# mainboard.net
KiCad netlist of a schematic drawn in EAGLE
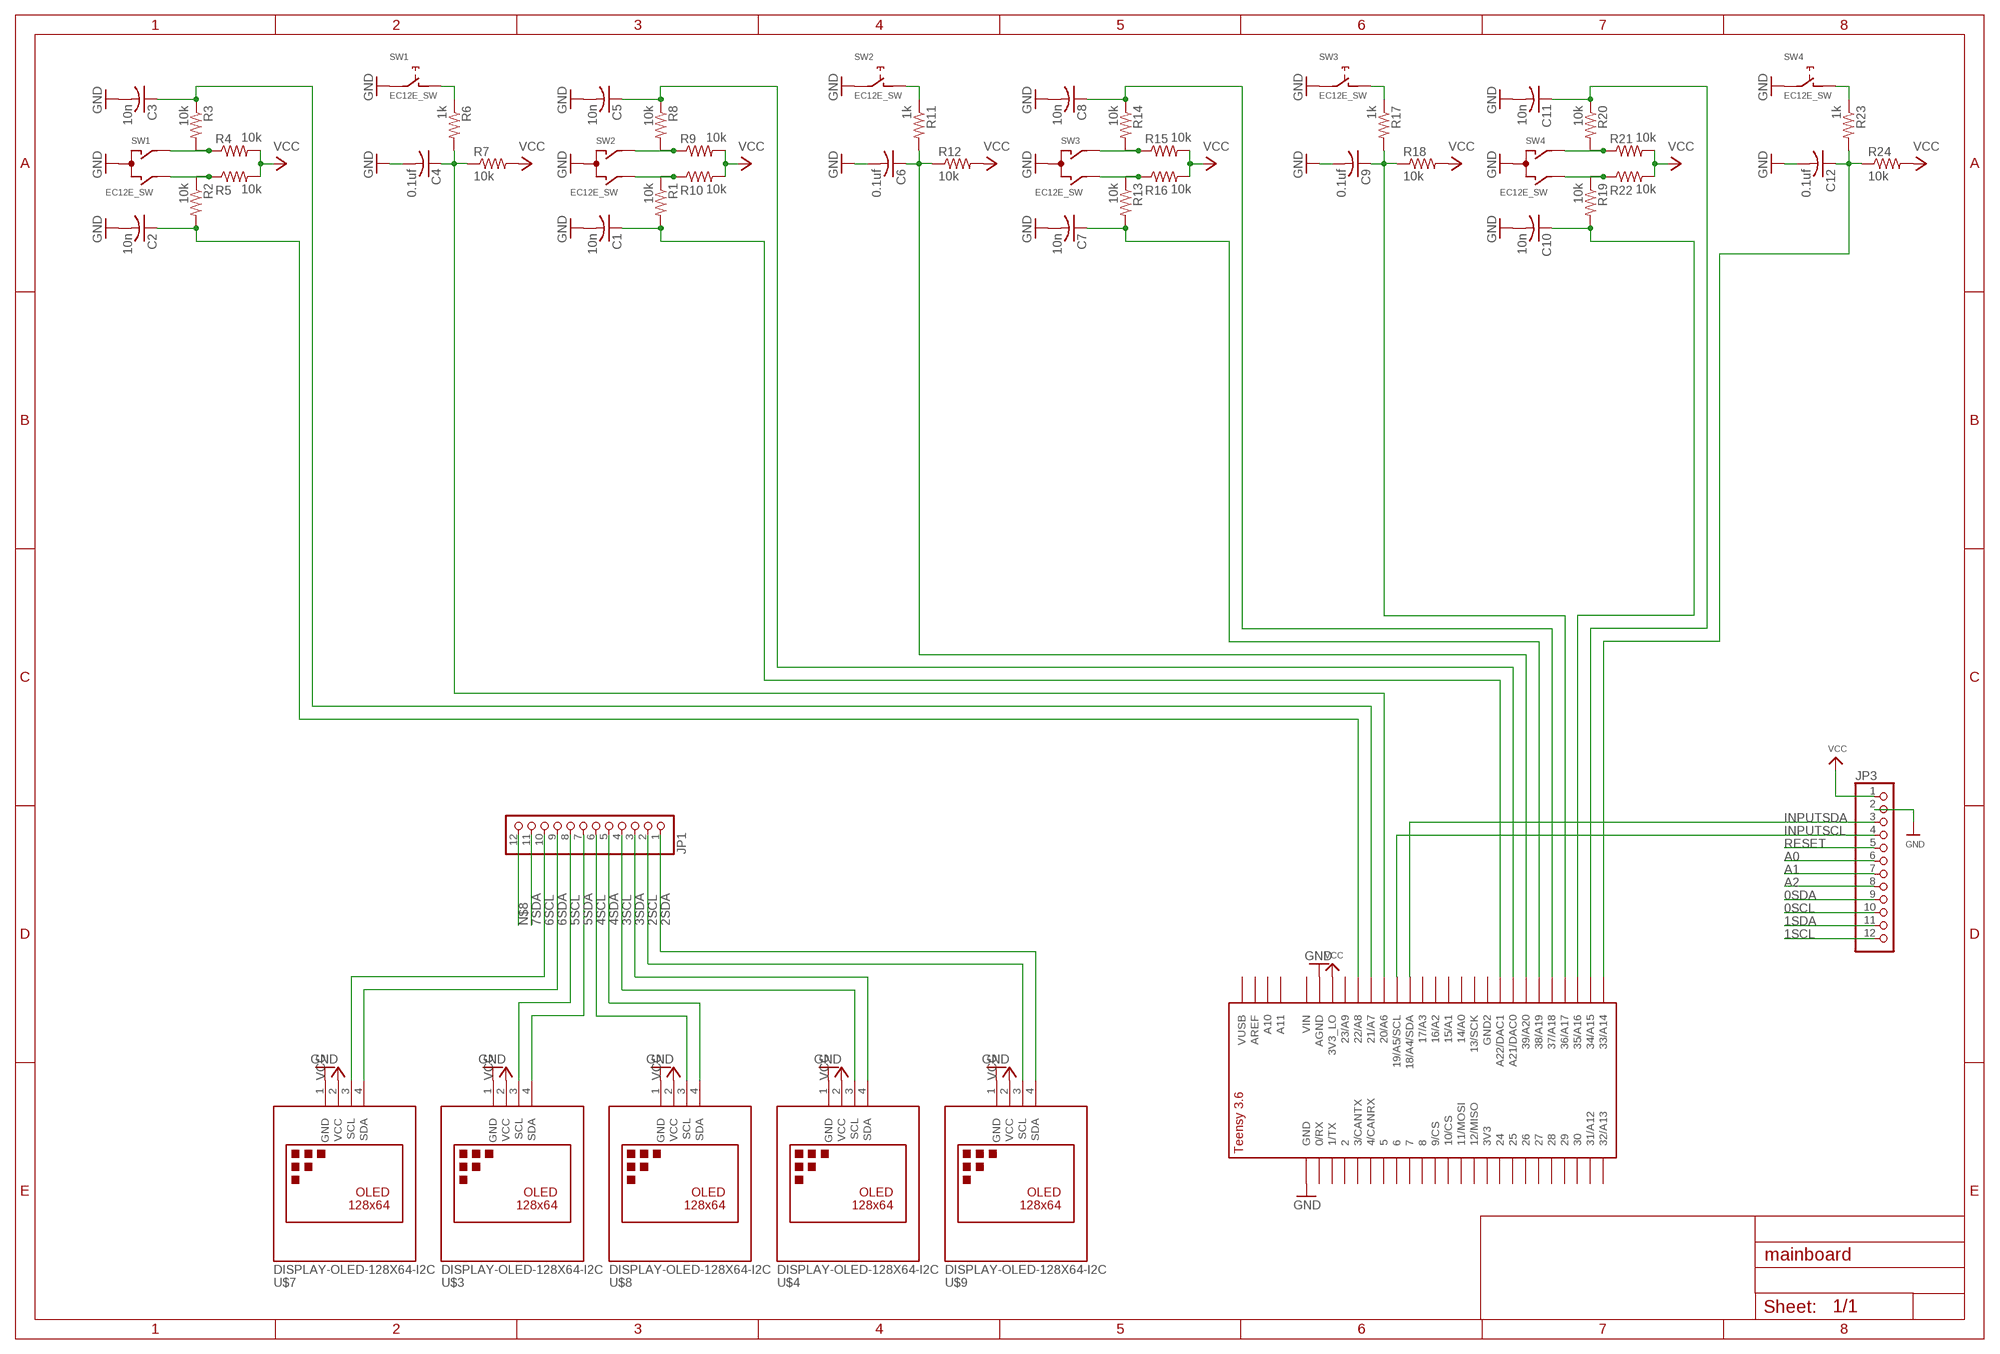
[diagram p0: schematic, sheet 1]

(export (version "E")
  (design (tool "Eeschema 10.0.6"))
  (components
    (comp (ref "C1")
      (value "10n")
      (footprint "eagle-import:C050-025X075")
      (libsource (lib "eagle-import") (part "C-US050-025X075"))
    )
    (comp (ref "C2")
      (value "10n")
      (footprint "eagle-import:C050-025X075")
      (libsource (lib "eagle-import") (part "C-US050-025X075"))
    )
    (comp (ref "C3")
      (value "10n")
      (footprint "eagle-import:C050-025X075")
      (libsource (lib "eagle-import") (part "C-US050-025X075"))
    )
    (comp (ref "C4")
      (value "0.1uf")
      (footprint "eagle-import:C050-025X075")
      (libsource (lib "eagle-import") (part "C-US050-025X075"))
    )
    (comp (ref "C5")
      (value "10n")
      (footprint "eagle-import:C050-025X075")
      (libsource (lib "eagle-import") (part "C-US050-025X075"))
    )
    (comp (ref "C6")
      (value "0.1uf")
      (footprint "eagle-import:C050-025X075")
      (libsource (lib "eagle-import") (part "C-US050-025X075"))
    )
    (comp (ref "C7")
      (value "10n")
      (footprint "eagle-import:C050-025X075")
      (libsource (lib "eagle-import") (part "C-US050-025X075"))
    )
    (comp (ref "C8")
      (value "10n")
      (footprint "eagle-import:C050-025X075")
      (libsource (lib "eagle-import") (part "C-US050-025X075"))
    )
    (comp (ref "C9")
      (value "0.1uf")
      (footprint "eagle-import:C050-025X075")
      (libsource (lib "eagle-import") (part "C-US050-025X075"))
    )
    (comp (ref "C10")
      (value "10n")
      (footprint "eagle-import:C050-025X075")
      (libsource (lib "eagle-import") (part "C-US050-025X075"))
    )
    (comp (ref "C11")
      (value "10n")
      (footprint "eagle-import:C050-025X075")
      (libsource (lib "eagle-import") (part "C-US050-025X075"))
    )
    (comp (ref "C12")
      (value "0.1uf")
      (footprint "eagle-import:C050-025X075")
      (libsource (lib "eagle-import") (part "C-US050-025X075"))
    )
    (comp (ref "JP1")
      (value "HEADER-1X12")
      (footprint "eagle-import:1X12_ROUND")
      (libsource (lib "eagle-import") (part "HEADER-1X12"))
    )
    (comp (ref "JP3")
      (value "HEADER-1X12")
      (footprint "eagle-import:1X12_ROUND")
      (libsource (lib "eagle-import") (part "HEADER-1X12"))
    )
    (comp (ref "R1")
      (value "10k")
      (footprint "eagle-import:0207_9")
      (libsource (lib "eagle-import") (part "R-US_0207/9"))
    )
    (comp (ref "R2")
      (value "10k")
      (footprint "eagle-import:0207_9")
      (libsource (lib "eagle-import") (part "R-US_0207/9"))
    )
    (comp (ref "R3")
      (value "10k")
      (footprint "eagle-import:0207_9")
      (libsource (lib "eagle-import") (part "R-US_0207/9"))
    )
    (comp (ref "R4")
      (value "10k")
      (footprint "eagle-import:0207_9")
      (libsource (lib "eagle-import") (part "R-US_0207/9"))
    )
    (comp (ref "R5")
      (value "10k")
      (footprint "eagle-import:0207_9")
      (libsource (lib "eagle-import") (part "R-US_0207/9"))
    )
    (comp (ref "R6")
      (value "1k")
      (footprint "eagle-import:0207_9")
      (libsource (lib "eagle-import") (part "R-US_0207/9"))
    )
    (comp (ref "R7")
      (value "10k")
      (footprint "eagle-import:0207_9")
      (libsource (lib "eagle-import") (part "R-US_0207/9"))
    )
    (comp (ref "R8")
      (value "10k")
      (footprint "eagle-import:0207_9")
      (libsource (lib "eagle-import") (part "R-US_0207/9"))
    )
    (comp (ref "R9")
      (value "10k")
      (footprint "eagle-import:0207_9")
      (libsource (lib "eagle-import") (part "R-US_0207/9"))
    )
    (comp (ref "R10")
      (value "10k")
      (footprint "eagle-import:0207_9")
      (libsource (lib "eagle-import") (part "R-US_0207/9"))
    )
    (comp (ref "R11")
      (value "1k")
      (footprint "eagle-import:0207_9")
      (libsource (lib "eagle-import") (part "R-US_0207/9"))
    )
    (comp (ref "R12")
      (value "10k")
      (footprint "eagle-import:0207_9")
      (libsource (lib "eagle-import") (part "R-US_0207/9"))
    )
    (comp (ref "R13")
      (value "10k")
      (footprint "eagle-import:0207_9")
      (libsource (lib "eagle-import") (part "R-US_0207/9"))
    )
    (comp (ref "R14")
      (value "10k")
      (footprint "eagle-import:0207_9")
      (libsource (lib "eagle-import") (part "R-US_0207/9"))
    )
    (comp (ref "R15")
      (value "10k")
      (footprint "eagle-import:0207_9")
      (libsource (lib "eagle-import") (part "R-US_0207/9"))
    )
    (comp (ref "R16")
      (value "10k")
      (footprint "eagle-import:0207_9")
      (libsource (lib "eagle-import") (part "R-US_0207/9"))
    )
    (comp (ref "R17")
      (value "1k")
      (footprint "eagle-import:0207_9")
      (libsource (lib "eagle-import") (part "R-US_0207/9"))
    )
    (comp (ref "R18")
      (value "10k")
      (footprint "eagle-import:0207_9")
      (libsource (lib "eagle-import") (part "R-US_0207/9"))
    )
    (comp (ref "R19")
      (value "10k")
      (footprint "eagle-import:0207_9")
      (libsource (lib "eagle-import") (part "R-US_0207/9"))
    )
    (comp (ref "R20")
      (value "10k")
      (footprint "eagle-import:0207_9")
      (libsource (lib "eagle-import") (part "R-US_0207/9"))
    )
    (comp (ref "R21")
      (value "10k")
      (footprint "eagle-import:0207_9")
      (libsource (lib "eagle-import") (part "R-US_0207/9"))
    )
    (comp (ref "R22")
      (value "10k")
      (footprint "eagle-import:0207_9")
      (libsource (lib "eagle-import") (part "R-US_0207/9"))
    )
    (comp (ref "R23")
      (value "1k")
      (footprint "eagle-import:0207_9")
      (libsource (lib "eagle-import") (part "R-US_0207/9"))
    )
    (comp (ref "R24")
      (value "10k")
      (footprint "eagle-import:0207_9")
      (libsource (lib "eagle-import") (part "R-US_0207/9"))
    )
    (comp (ref "SW1")
      (value "EC12E_SW")
      (footprint "eagle-import:ALPS_EC12E_SW")
      (fields (field (name "MPN") "EC12E2424407"))
      (libsource (lib "eagle-import") (part "EC12E_SW"))
    )
    (comp (ref "SW2")
      (value "EC12E_SW")
      (footprint "eagle-import:ALPS_EC12E_SW")
      (fields (field (name "MPN") "EC12E2424407"))
      (libsource (lib "eagle-import") (part "EC12E_SW"))
    )
    (comp (ref "SW3")
      (value "EC12E_SW")
      (footprint "eagle-import:ALPS_EC12E_SW")
      (fields (field (name "MPN") "EC12E2424407"))
      (libsource (lib "eagle-import") (part "EC12E_SW"))
    )
    (comp (ref "SW4")
      (value "EC12E_SW")
      (footprint "eagle-import:ALPS_EC12E_SW")
      (fields (field (name "MPN") "EC12E2424407"))
      (libsource (lib "eagle-import") (part "EC12E_SW"))
    )
    (comp (ref "U$1")
      (value "TEENSY_3.5/3.6_BASIC")
      (footprint "eagle-import:TEENSY_3.5_3.6_BASIC")
      (libsource (lib "eagle-import") (part "TEENSY_3.5/3.6_BASIC"))
    )
    (comp (ref "U$3")
      (value "DISPLAY-OLED-128X64-I2C")
      (footprint "eagle-import:DISPLAY-OLED-128X64-I2C")
      (libsource (lib "eagle-import") (part "DISPLAY-OLED-128X64-I2C"))
    )
    (comp (ref "U$4")
      (value "DISPLAY-OLED-128X64-I2C")
      (footprint "eagle-import:DISPLAY-OLED-128X64-I2C")
      (libsource (lib "eagle-import") (part "DISPLAY-OLED-128X64-I2C"))
    )
    (comp (ref "U$7")
      (value "DISPLAY-OLED-128X64-I2C")
      (footprint "eagle-import:DISPLAY-OLED-128X64-I2C")
      (libsource (lib "eagle-import") (part "DISPLAY-OLED-128X64-I2C"))
    )
    (comp (ref "U$8")
      (value "DISPLAY-OLED-128X64-I2C")
      (footprint "eagle-import:DISPLAY-OLED-128X64-I2C")
      (libsource (lib "eagle-import") (part "DISPLAY-OLED-128X64-I2C"))
    )
    (comp (ref "U$9")
      (value "DISPLAY-OLED-128X64-I2C")
      (footprint "eagle-import:DISPLAY-OLED-128X64-I2C")
      (libsource (lib "eagle-import") (part "DISPLAY-OLED-128X64-I2C"))
    )
  )
  (nets
    (net (code "1") (name "/0SCL") (class "Default")
      (node (ref "JP3") (pin "10") (pinfunction "10_10") (pintype "passive"))
    )
    (net (code "2") (name "/0SDA") (class "Default")
      (node (ref "JP3") (pin "9") (pinfunction "9_9") (pintype "passive"))
    )
    (net (code "3") (name "/1SCL") (class "Default")
      (node (ref "JP3") (pin "12") (pinfunction "12_12") (pintype "passive"))
    )
    (net (code "4") (name "/1SDA") (class "Default")
      (node (ref "JP3") (pin "11") (pinfunction "11_11") (pintype "passive"))
    )
    (net (code "5") (name "/2SCL") (class "Default")
      (node (ref "JP1") (pin "2") (pinfunction "2_2") (pintype "passive"))
      (node (ref "U$9") (pin "3") (pinfunction "SCL_3") (pintype "bidirectional"))
    )
    (net (code "6") (name "/2SDA") (class "Default")
      (node (ref "JP1") (pin "1") (pinfunction "1_1") (pintype "passive"))
      (node (ref "U$9") (pin "4") (pinfunction "SDA_4") (pintype "bidirectional"))
    )
    (net (code "7") (name "/3SCL") (class "Default")
      (node (ref "JP1") (pin "4") (pinfunction "4_4") (pintype "passive"))
      (node (ref "U$4") (pin "3") (pinfunction "SCL_3") (pintype "bidirectional"))
    )
    (net (code "8") (name "/3SDA") (class "Default")
      (node (ref "JP1") (pin "3") (pinfunction "3_3") (pintype "passive"))
      (node (ref "U$4") (pin "4") (pinfunction "SDA_4") (pintype "bidirectional"))
    )
    (net (code "9") (name "/4SCL") (class "Default")
      (node (ref "JP1") (pin "6") (pinfunction "6_6") (pintype "passive"))
      (node (ref "U$8") (pin "3") (pinfunction "SCL_3") (pintype "bidirectional"))
    )
    (net (code "10") (name "/4SDA") (class "Default")
      (node (ref "JP1") (pin "5") (pinfunction "5_5") (pintype "passive"))
      (node (ref "U$8") (pin "4") (pinfunction "SDA_4") (pintype "bidirectional"))
    )
    (net (code "11") (name "/5SCL") (class "Default")
      (node (ref "JP1") (pin "8") (pinfunction "8_8") (pintype "passive"))
      (node (ref "U$3") (pin "3") (pinfunction "SCL_3") (pintype "bidirectional"))
    )
    (net (code "12") (name "/5SDA") (class "Default")
      (node (ref "JP1") (pin "7") (pinfunction "7_7") (pintype "passive"))
      (node (ref "U$3") (pin "4") (pinfunction "SDA_4") (pintype "bidirectional"))
    )
    (net (code "13") (name "/6SCL") (class "Default")
      (node (ref "JP1") (pin "10") (pinfunction "10_10") (pintype "passive"))
      (node (ref "U$7") (pin "3") (pinfunction "SCL_3") (pintype "bidirectional"))
    )
    (net (code "14") (name "/6SDA") (class "Default")
      (node (ref "JP1") (pin "9") (pinfunction "9_9") (pintype "passive"))
      (node (ref "U$7") (pin "4") (pinfunction "SDA_4") (pintype "bidirectional"))
    )
    (net (code "15") (name "/7SDA") (class "Default")
      (node (ref "JP1") (pin "11") (pinfunction "11_11") (pintype "passive"))
    )
    (net (code "16") (name "/A0") (class "Default")
      (node (ref "JP3") (pin "6") (pinfunction "6_6") (pintype "passive"))
    )
    (net (code "17") (name "/A1") (class "Default")
      (node (ref "JP3") (pin "7") (pinfunction "7_7") (pintype "passive"))
    )
    (net (code "18") (name "/A2") (class "Default")
      (node (ref "JP3") (pin "8") (pinfunction "8_8") (pintype "passive"))
    )
    (net (code "19") (name "/INPUTSCL") (class "Default")
      (node (ref "JP3") (pin "4") (pinfunction "4_4") (pintype "passive"))
      (node (ref "U$1") (pin "19/A5/SCL") (pinfunction "19/A5/SCL_19/A5/SCL") (pintype "bidirectional"))
    )
    (net (code "20") (name "/INPUTSDA") (class "Default")
      (node (ref "JP3") (pin "3") (pinfunction "3_3") (pintype "passive"))
      (node (ref "U$1") (pin "18/A4/SDA") (pinfunction "18/A4/SDA_18/A4/SDA") (pintype "bidirectional"))
    )
    (net (code "21") (name "/N$8") (class "Default")
      (node (ref "JP1") (pin "12") (pinfunction "12_12") (pintype "passive"))
    )
    (net (code "22") (name "/RESET") (class "Default")
      (node (ref "JP3") (pin "5") (pinfunction "5_5") (pintype "passive"))
    )
    (net (code "23") (name "GND") (class "Default")
      (node (ref "C1") (pin "2") (pinfunction "2_2") (pintype "passive"))
      (node (ref "C10") (pin "2") (pinfunction "2_2") (pintype "passive"))
      (node (ref "C11") (pin "2") (pinfunction "2_2") (pintype "passive"))
      (node (ref "C12") (pin "2") (pinfunction "2_2") (pintype "passive"))
      (node (ref "C2") (pin "2") (pinfunction "2_2") (pintype "passive"))
      (node (ref "C3") (pin "2") (pinfunction "2_2") (pintype "passive"))
      (node (ref "C4") (pin "2") (pinfunction "2_2") (pintype "passive"))
      (node (ref "C5") (pin "2") (pinfunction "2_2") (pintype "passive"))
      (node (ref "C6") (pin "2") (pinfunction "2_2") (pintype "passive"))
      (node (ref "C7") (pin "2") (pinfunction "2_2") (pintype "passive"))
      (node (ref "C8") (pin "2") (pinfunction "2_2") (pintype "passive"))
      (node (ref "C9") (pin "2") (pinfunction "2_2") (pintype "passive"))
      (node (ref "JP3") (pin "2") (pinfunction "2_2") (pintype "passive"))
      (node (ref "SW1") (pin "C") (pinfunction "C_C") (pintype "passive"))
      (node (ref "SW1") (pin "E") (pinfunction "2_E") (pintype "passive"))
      (node (ref "SW2") (pin "C") (pinfunction "C_C") (pintype "passive"))
      (node (ref "SW2") (pin "E") (pinfunction "2_E") (pintype "passive"))
      (node (ref "SW3") (pin "C") (pinfunction "C_C") (pintype "passive"))
      (node (ref "SW3") (pin "E") (pinfunction "2_E") (pintype "passive"))
      (node (ref "SW4") (pin "C") (pinfunction "C_C") (pintype "passive"))
      (node (ref "SW4") (pin "E") (pinfunction "2_E") (pintype "passive"))
      (node (ref "U$1") (pin "AGND") (pinfunction "AGND_AGND") (pintype "bidirectional"))
      (node (ref "U$1") (pin "GND") (pinfunction "GND_GND") (pintype "bidirectional"))
      (node (ref "U$3") (pin "1") (pinfunction "GND_1") (pintype "power_in"))
      (node (ref "U$4") (pin "1") (pinfunction "GND_1") (pintype "power_in"))
      (node (ref "U$7") (pin "1") (pinfunction "GND_1") (pintype "power_in"))
      (node (ref "U$8") (pin "1") (pinfunction "GND_1") (pintype "power_in"))
      (node (ref "U$9") (pin "1") (pinfunction "GND_1") (pintype "power_in"))
    )
    (net (code "24") (name "Net-(C1-Pad1)") (class "Default")
      (node (ref "C1") (pin "1") (pinfunction "1_1") (pintype "passive"))
      (node (ref "R1") (pin "2") (pinfunction "2_2") (pintype "passive"))
      (node (ref "U$1") (pin "A22/DAC1") (pinfunction "A22/DAC1_A22/DAC1") (pintype "bidirectional"))
    )
    (net (code "25") (name "Net-(C2-Pad1)") (class "Default")
      (node (ref "C2") (pin "1") (pinfunction "1_1") (pintype "passive"))
      (node (ref "R2") (pin "2") (pinfunction "2_2") (pintype "passive"))
      (node (ref "U$1") (pin "22/A8") (pinfunction "22/A8_22/A8") (pintype "bidirectional"))
    )
    (net (code "26") (name "Net-(C3-Pad1)") (class "Default")
      (node (ref "C3") (pin "1") (pinfunction "1_1") (pintype "passive"))
      (node (ref "R3") (pin "1") (pinfunction "1_1") (pintype "passive"))
      (node (ref "U$1") (pin "21/A7") (pinfunction "21/A7_21/A7") (pintype "bidirectional"))
    )
    (net (code "27") (name "Net-(C4-Pad1)") (class "Default")
      (node (ref "C4") (pin "1") (pinfunction "1_1") (pintype "passive"))
      (node (ref "R6") (pin "2") (pinfunction "2_2") (pintype "passive"))
      (node (ref "R7") (pin "1") (pinfunction "1_1") (pintype "passive"))
      (node (ref "U$1") (pin "20/A6") (pinfunction "20/A6_20/A6") (pintype "bidirectional"))
    )
    (net (code "28") (name "Net-(C6-Pad1)") (class "Default")
      (node (ref "C6") (pin "1") (pinfunction "1_1") (pintype "passive"))
      (node (ref "R11") (pin "2") (pinfunction "2_2") (pintype "passive"))
      (node (ref "R12") (pin "1") (pinfunction "1_1") (pintype "passive"))
      (node (ref "U$1") (pin "39/A20") (pinfunction "39/A20_39/A20") (pintype "bidirectional"))
    )
    (net (code "29") (name "Net-(C7-Pad1)") (class "Default")
      (node (ref "C7") (pin "1") (pinfunction "1_1") (pintype "passive"))
      (node (ref "R13") (pin "2") (pinfunction "2_2") (pintype "passive"))
      (node (ref "U$1") (pin "38/A19") (pinfunction "38/A19_38/A19") (pintype "bidirectional"))
    )
    (net (code "30") (name "Net-(C8-Pad1)") (class "Default")
      (node (ref "C8") (pin "1") (pinfunction "1_1") (pintype "passive"))
      (node (ref "R14") (pin "1") (pinfunction "1_1") (pintype "passive"))
      (node (ref "U$1") (pin "37/A18") (pinfunction "37/A18_37/A18") (pintype "bidirectional"))
    )
    (net (code "31") (name "Net-(C9-Pad1)") (class "Default")
      (node (ref "C9") (pin "1") (pinfunction "1_1") (pintype "passive"))
      (node (ref "R17") (pin "2") (pinfunction "2_2") (pintype "passive"))
      (node (ref "R18") (pin "1") (pinfunction "1_1") (pintype "passive"))
      (node (ref "U$1") (pin "36/A17") (pinfunction "36/A17_36/A17") (pintype "bidirectional"))
    )
    (net (code "32") (name "Net-(C10-Pad1)") (class "Default")
      (node (ref "C10") (pin "1") (pinfunction "1_1") (pintype "passive"))
      (node (ref "R19") (pin "2") (pinfunction "2_2") (pintype "passive"))
      (node (ref "U$1") (pin "35/A16") (pinfunction "35/A16_35/A16") (pintype "bidirectional"))
    )
    (net (code "33") (name "Net-(C11-Pad1)") (class "Default")
      (node (ref "C11") (pin "1") (pinfunction "1_1") (pintype "passive"))
      (node (ref "R20") (pin "1") (pinfunction "1_1") (pintype "passive"))
      (node (ref "U$1") (pin "34/A15") (pinfunction "34/A15_34/A15") (pintype "bidirectional"))
    )
    (net (code "34") (name "Net-(C12-Pad1)") (class "Default")
      (node (ref "C12") (pin "1") (pinfunction "1_1") (pintype "passive"))
      (node (ref "R23") (pin "2") (pinfunction "2_2") (pintype "passive"))
      (node (ref "R24") (pin "1") (pinfunction "1_1") (pintype "passive"))
      (node (ref "U$1") (pin "33/A14") (pinfunction "33/A14_33/A14") (pintype "bidirectional"))
    )
    (net (code "35") (name "Net-(R1-Pad1)") (class "Default")
      (node (ref "R1") (pin "1") (pinfunction "1_1") (pintype "passive"))
      (node (ref "R10") (pin "1") (pinfunction "1_1") (pintype "passive"))
      (node (ref "SW2") (pin "B") (pinfunction "B_B") (pintype "passive"))
    )
    (net (code "36") (name "Net-(R2-Pad1)") (class "Default")
      (node (ref "R2") (pin "1") (pinfunction "1_1") (pintype "passive"))
      (node (ref "R5") (pin "1") (pinfunction "1_1") (pintype "passive"))
      (node (ref "SW1") (pin "B") (pinfunction "B_B") (pintype "passive"))
    )
    (net (code "37") (name "Net-(R3-Pad2)") (class "Default")
      (node (ref "R3") (pin "2") (pinfunction "2_2") (pintype "passive"))
      (node (ref "R4") (pin "1") (pinfunction "1_1") (pintype "passive"))
      (node (ref "SW1") (pin "A") (pinfunction "A_A") (pintype "passive"))
    )
    (net (code "38") (name "Net-(R8-Pad2)") (class "Default")
      (node (ref "R8") (pin "2") (pinfunction "2_2") (pintype "passive"))
      (node (ref "R9") (pin "1") (pinfunction "1_1") (pintype "passive"))
      (node (ref "SW2") (pin "A") (pinfunction "A_A") (pintype "passive"))
    )
    (net (code "39") (name "Net-(R13-Pad1)") (class "Default")
      (node (ref "R13") (pin "1") (pinfunction "1_1") (pintype "passive"))
      (node (ref "R16") (pin "1") (pinfunction "1_1") (pintype "passive"))
      (node (ref "SW3") (pin "B") (pinfunction "B_B") (pintype "passive"))
    )
    (net (code "40") (name "Net-(R14-Pad2)") (class "Default")
      (node (ref "R14") (pin "2") (pinfunction "2_2") (pintype "passive"))
      (node (ref "R15") (pin "1") (pinfunction "1_1") (pintype "passive"))
      (node (ref "SW3") (pin "A") (pinfunction "A_A") (pintype "passive"))
    )
    (net (code "41") (name "Net-(R19-Pad1)") (class "Default")
      (node (ref "R19") (pin "1") (pinfunction "1_1") (pintype "passive"))
      (node (ref "R22") (pin "1") (pinfunction "1_1") (pintype "passive"))
      (node (ref "SW4") (pin "B") (pinfunction "B_B") (pintype "passive"))
    )
    (net (code "42") (name "Net-(R20-Pad2)") (class "Default")
      (node (ref "R20") (pin "2") (pinfunction "2_2") (pintype "passive"))
      (node (ref "R21") (pin "1") (pinfunction "1_1") (pintype "passive"))
      (node (ref "SW4") (pin "A") (pinfunction "A_A") (pintype "passive"))
    )
    (net (code "43") (name "Net-(SW1B-1)") (class "Default")
      (node (ref "R6") (pin "1") (pinfunction "1_1") (pintype "passive"))
      (node (ref "SW1") (pin "D") (pinfunction "1_D") (pintype "passive"))
    )
    (net (code "44") (name "Net-(SW2B-1)") (class "Default")
      (node (ref "R11") (pin "1") (pinfunction "1_1") (pintype "passive"))
      (node (ref "SW2") (pin "D") (pinfunction "1_D") (pintype "passive"))
    )
    (net (code "45") (name "Net-(SW3B-1)") (class "Default")
      (node (ref "R17") (pin "1") (pinfunction "1_1") (pintype "passive"))
      (node (ref "SW3") (pin "D") (pinfunction "1_D") (pintype "passive"))
    )
    (net (code "46") (name "Net-(SW4B-1)") (class "Default")
      (node (ref "R23") (pin "1") (pinfunction "1_1") (pintype "passive"))
      (node (ref "SW4") (pin "D") (pinfunction "1_D") (pintype "passive"))
    )
    (net (code "47") (name "Net-(U$1-A21{slash}DAC0)") (class "Default")
      (node (ref "C5") (pin "1") (pinfunction "1_1") (pintype "passive"))
      (node (ref "R8") (pin "1") (pinfunction "1_1") (pintype "passive"))
      (node (ref "U$1") (pin "21/DAC0") (pinfunction "A21/DAC0_21/DAC0") (pintype "bidirectional"))
    )
    (net (code "48") (name "VCC") (class "Default")
      (node (ref "JP3") (pin "1") (pinfunction "1_1") (pintype "passive"))
      (node (ref "R10") (pin "2") (pinfunction "2_2") (pintype "passive"))
      (node (ref "R12") (pin "2") (pinfunction "2_2") (pintype "passive"))
      (node (ref "R15") (pin "2") (pinfunction "2_2") (pintype "passive"))
      (node (ref "R16") (pin "2") (pinfunction "2_2") (pintype "passive"))
      (node (ref "R18") (pin "2") (pinfunction "2_2") (pintype "passive"))
      (node (ref "R21") (pin "2") (pinfunction "2_2") (pintype "passive"))
      (node (ref "R22") (pin "2") (pinfunction "2_2") (pintype "passive"))
      (node (ref "R24") (pin "2") (pinfunction "2_2") (pintype "passive"))
      (node (ref "R4") (pin "2") (pinfunction "2_2") (pintype "passive"))
      (node (ref "R5") (pin "2") (pinfunction "2_2") (pintype "passive"))
      (node (ref "R7") (pin "2") (pinfunction "2_2") (pintype "passive"))
      (node (ref "R9") (pin "2") (pinfunction "2_2") (pintype "passive"))
      (node (ref "U$1") (pin "3V3_LO") (pinfunction "3V3_LO_3V3_LO") (pintype "bidirectional"))
      (node (ref "U$3") (pin "2") (pinfunction "VCC_2") (pintype "power_in"))
      (node (ref "U$4") (pin "2") (pinfunction "VCC_2") (pintype "power_in"))
      (node (ref "U$7") (pin "2") (pinfunction "VCC_2") (pintype "power_in"))
      (node (ref "U$8") (pin "2") (pinfunction "VCC_2") (pintype "power_in"))
      (node (ref "U$9") (pin "2") (pinfunction "VCC_2") (pintype "power_in"))
    )
    (net (code "49") (name "unconnected-(U$1-Pad0{slash}RX)") (class "Default")
      (node (ref "U$1") (pin "0/RX") (pinfunction "0/RX_0/RX") (pintype "bidirectional"))
    )
    (net (code "50") (name "unconnected-(U$1-Pad1{slash}TX)") (class "Default")
      (node (ref "U$1") (pin "1/TX") (pinfunction "1/TX_1/TX") (pintype "bidirectional"))
    )
    (net (code "51") (name "unconnected-(U$1-Pad2)") (class "Default")
      (node (ref "U$1") (pin "2") (pinfunction "2_2") (pintype "bidirectional"))
    )
    (net (code "52") (name "unconnected-(U$1-Pad3V3)") (class "Default")
      (node (ref "U$1") (pin "3V3") (pinfunction "3V3_3V3") (pintype "bidirectional"))
    )
    (net (code "53") (name "unconnected-(U$1-Pad3{slash}CANTX)") (class "Default")
      (node (ref "U$1") (pin "3/CANTX") (pinfunction "3/CANTX_3/CANTX") (pintype "bidirectional"))
    )
    (net (code "54") (name "unconnected-(U$1-Pad4{slash}CANRX)") (class "Default")
      (node (ref "U$1") (pin "4/CANRX") (pinfunction "4/CANRX_4/CANRX") (pintype "bidirectional"))
    )
    (net (code "55") (name "unconnected-(U$1-Pad5)") (class "Default")
      (node (ref "U$1") (pin "5") (pinfunction "5_5") (pintype "bidirectional"))
    )
    (net (code "56") (name "unconnected-(U$1-Pad6)") (class "Default")
      (node (ref "U$1") (pin "6") (pinfunction "6_6") (pintype "bidirectional"))
    )
    (net (code "57") (name "unconnected-(U$1-Pad7)") (class "Default")
      (node (ref "U$1") (pin "7") (pinfunction "7_7") (pintype "bidirectional"))
    )
    (net (code "58") (name "unconnected-(U$1-Pad8)") (class "Default")
      (node (ref "U$1") (pin "8") (pinfunction "8_8") (pintype "bidirectional"))
    )
    (net (code "59") (name "unconnected-(U$1-Pad9{slash}CS)") (class "Default")
      (node (ref "U$1") (pin "9/CS") (pinfunction "9/CS_9/CS") (pintype "bidirectional"))
    )
    (net (code "60") (name "unconnected-(U$1-Pad10{slash}CS)") (class "Default")
      (node (ref "U$1") (pin "10/CS") (pinfunction "10/CS_10/CS") (pintype "bidirectional"))
    )
    (net (code "61") (name "unconnected-(U$1-Pad11{slash}MOSI)") (class "Default")
      (node (ref "U$1") (pin "11/MOSI") (pinfunction "11/MOSI_11/MOSI") (pintype "bidirectional"))
    )
    (net (code "62") (name "unconnected-(U$1-Pad12{slash}MISO)") (class "Default")
      (node (ref "U$1") (pin "12/MISO") (pinfunction "12/MISO_12/MISO") (pintype "bidirectional"))
    )
    (net (code "63") (name "unconnected-(U$1-Pad13{slash}SCK)") (class "Default")
      (node (ref "U$1") (pin "13/SCK") (pinfunction "13/SCK_13/SCK") (pintype "bidirectional"))
    )
    (net (code "64") (name "unconnected-(U$1-Pad14{slash}A0)") (class "Default")
      (node (ref "U$1") (pin "14/A0") (pinfunction "14/A0_14/A0") (pintype "bidirectional"))
    )
    (net (code "65") (name "unconnected-(U$1-Pad15{slash}A1)") (class "Default")
      (node (ref "U$1") (pin "15/A1") (pinfunction "15/A1_15/A1") (pintype "bidirectional"))
    )
    (net (code "66") (name "unconnected-(U$1-Pad16{slash}A2)") (class "Default")
      (node (ref "U$1") (pin "16/A2") (pinfunction "16/A2_16/A2") (pintype "bidirectional"))
    )
    (net (code "67") (name "unconnected-(U$1-Pad17{slash}A3)") (class "Default")
      (node (ref "U$1") (pin "17/A3") (pinfunction "17/A3_17/A3") (pintype "bidirectional"))
    )
    (net (code "68") (name "unconnected-(U$1-Pad23{slash}A9)") (class "Default")
      (node (ref "U$1") (pin "23/A9") (pinfunction "23/A9_23/A9") (pintype "bidirectional"))
    )
    (net (code "69") (name "unconnected-(U$1-Pad24)") (class "Default")
      (node (ref "U$1") (pin "24") (pinfunction "24_24") (pintype "bidirectional"))
    )
    (net (code "70") (name "unconnected-(U$1-Pad25)") (class "Default")
      (node (ref "U$1") (pin "25") (pinfunction "25_25") (pintype "bidirectional"))
    )
    (net (code "71") (name "unconnected-(U$1-Pad26)") (class "Default")
      (node (ref "U$1") (pin "26") (pinfunction "26_26") (pintype "bidirectional"))
    )
    (net (code "72") (name "unconnected-(U$1-Pad27)") (class "Default")
      (node (ref "U$1") (pin "27") (pinfunction "27_27") (pintype "bidirectional"))
    )
    (net (code "73") (name "unconnected-(U$1-Pad28)") (class "Default")
      (node (ref "U$1") (pin "28") (pinfunction "28_28") (pintype "bidirectional"))
    )
    (net (code "74") (name "unconnected-(U$1-Pad29)") (class "Default")
      (node (ref "U$1") (pin "29") (pinfunction "29_29") (pintype "bidirectional"))
    )
    (net (code "75") (name "unconnected-(U$1-Pad30)") (class "Default")
      (node (ref "U$1") (pin "30") (pinfunction "30_30") (pintype "bidirectional"))
    )
    (net (code "76") (name "unconnected-(U$1-Pad31{slash}A12)") (class "Default")
      (node (ref "U$1") (pin "31/A12") (pinfunction "31/A12_31/A12") (pintype "bidirectional"))
    )
    (net (code "77") (name "unconnected-(U$1-Pad32{slash}A13)") (class "Default")
      (node (ref "U$1") (pin "32/A13") (pinfunction "32/A13_32/A13") (pintype "bidirectional"))
    )
    (net (code "78") (name "unconnected-(U$1-PadA10)") (class "Default")
      (node (ref "U$1") (pin "A10") (pinfunction "A10_A10") (pintype "bidirectional"))
    )
    (net (code "79") (name "unconnected-(U$1-PadA11)") (class "Default")
      (node (ref "U$1") (pin "A11") (pinfunction "A11_A11") (pintype "bidirectional"))
    )
    (net (code "80") (name "unconnected-(U$1-PadAREF)") (class "Default")
      (node (ref "U$1") (pin "AREF") (pinfunction "AREF_AREF") (pintype "bidirectional"))
    )
    (net (code "81") (name "unconnected-(U$1-PadGND2)") (class "Default")
      (node (ref "U$1") (pin "GND2") (pinfunction "GND2_GND2") (pintype "bidirectional"))
    )
    (net (code "82") (name "unconnected-(U$1-PadVIN)") (class "Default")
      (node (ref "U$1") (pin "VIN") (pinfunction "VIN_VIN") (pintype "bidirectional"))
    )
    (net (code "83") (name "unconnected-(U$1-PadVUSB)") (class "Default")
      (node (ref "U$1") (pin "VUSB") (pinfunction "VUSB_VUSB") (pintype "bidirectional"))
    )
  )
)
